# NMX-201-B.net
KiCad netlist of a schematic drawn in EAGLE
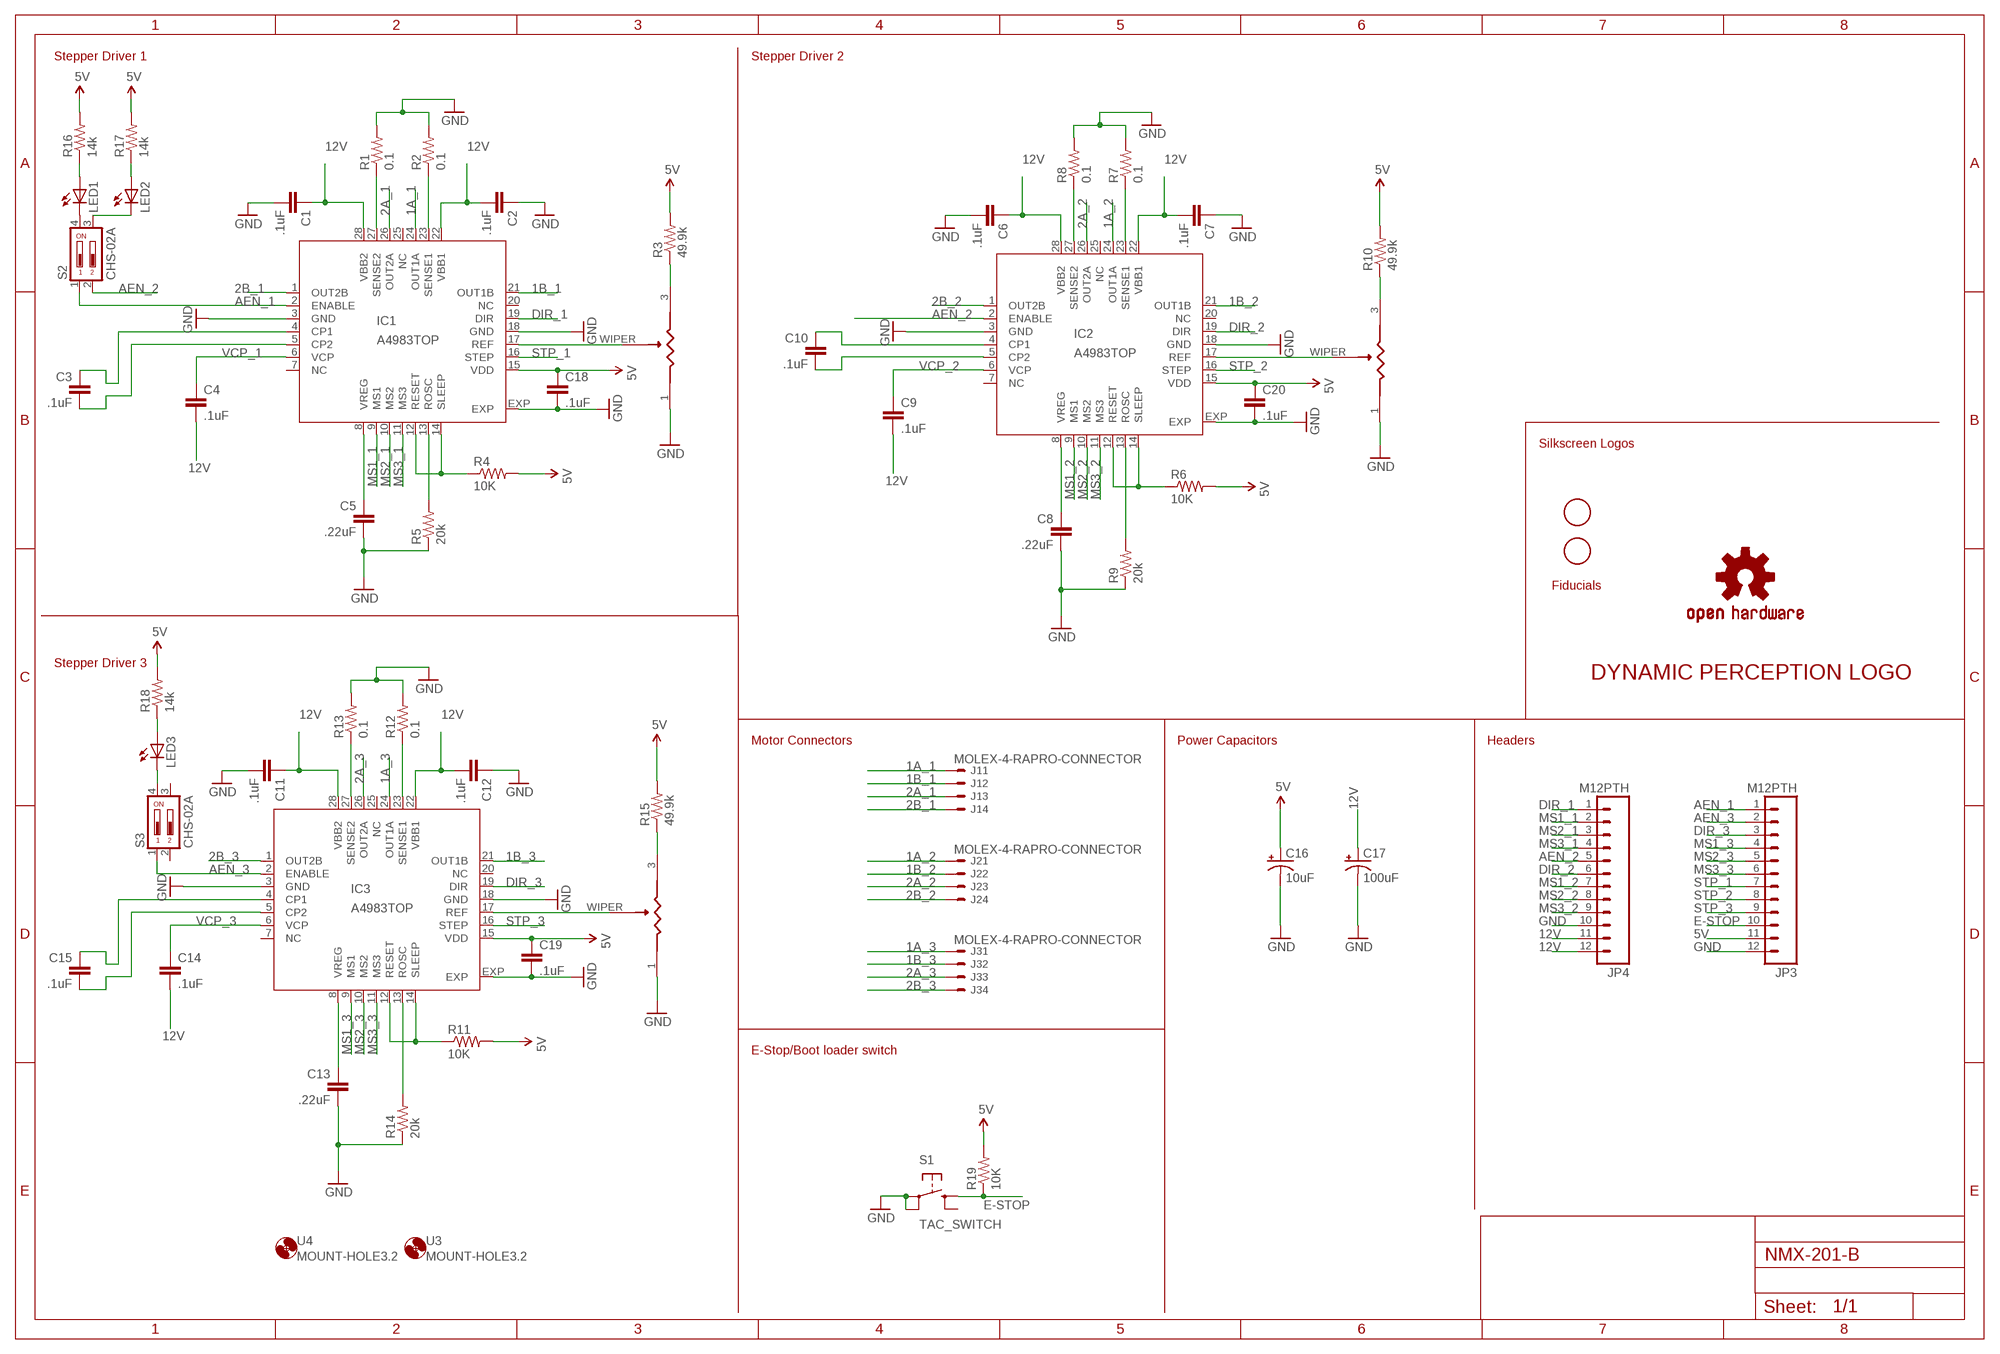
[diagram p0: schematic, sheet 1]

(export (version "E")
  (design (tool "Eeschema 10.0.6"))
  (components
    (comp (ref "C1")
      (value ".1uF")
      (footprint "eagle-import:0402-CAP")
      (fields (field (name "MF") "Taiyo Yuden") (field (name "MPN") "TMK105BJ104KV-F"))
      (libsource (lib "eagle-import") (part "CAP0402-CAP"))
    )
    (comp (ref "C2")
      (value ".1uF")
      (footprint "eagle-import:0402-CAP")
      (fields (field (name "MF") "Taiyo Yuden") (field (name "MPN") "TMK105BJ104KV-F"))
      (libsource (lib "eagle-import") (part "CAP0402-CAP"))
    )
    (comp (ref "C3")
      (value ".1uF")
      (footprint "eagle-import:0402-CAP")
      (fields (field (name "MF") "Taiyo Yuden") (field (name "MPN") "TMK105BJ104KV-F"))
      (libsource (lib "eagle-import") (part "CAP0402-CAP"))
    )
    (comp (ref "C4")
      (value ".1uF")
      (footprint "eagle-import:0402-CAP")
      (fields (field (name "MF") "Taiyo Yuden") (field (name "MPN") "TMK105BJ104KV-F"))
      (libsource (lib "eagle-import") (part "CAP0402-CAP"))
    )
    (comp (ref "C5")
      (value ".22uF")
      (footprint "eagle-import:0402-CAP")
      (fields (field (name "MF") "Taiyo Yuden") (field (name "MPN") "TMK105BJ224KVHF"))
      (libsource (lib "eagle-import") (part "CAP0402-CAP"))
    )
    (comp (ref "C6")
      (value ".1uF")
      (footprint "eagle-import:0402-CAP")
      (fields (field (name "MF") "Taiyo Yuden") (field (name "MPN") "TMK105BJ104KV-F"))
      (libsource (lib "eagle-import") (part "CAP0402-CAP"))
    )
    (comp (ref "C7")
      (value ".1uF")
      (footprint "eagle-import:0402-CAP")
      (fields (field (name "MF") "Taiyo Yuden") (field (name "MPN") "TMK105BJ104KV-F"))
      (libsource (lib "eagle-import") (part "CAP0402-CAP"))
    )
    (comp (ref "C8")
      (value ".22uF")
      (footprint "eagle-import:0402-CAP")
      (fields (field (name "MF") "Taiyo Yuden") (field (name "MPN") "TMK105BJ224KVHF"))
      (libsource (lib "eagle-import") (part "CAP0402-CAP"))
    )
    (comp (ref "C9")
      (value ".1uF")
      (footprint "eagle-import:0402-CAP")
      (fields (field (name "MF") "Taiyo Yuden") (field (name "MPN") "TMK105BJ104KV-F"))
      (libsource (lib "eagle-import") (part "CAP0402-CAP"))
    )
    (comp (ref "C10")
      (value ".1uF")
      (footprint "eagle-import:0402-CAP")
      (fields (field (name "MF") "Taiyo Yuden") (field (name "MPN") "TMK105BJ104KV-F"))
      (libsource (lib "eagle-import") (part "CAP0402-CAP"))
    )
    (comp (ref "C11")
      (value ".1uF")
      (footprint "eagle-import:0402-CAP")
      (fields (field (name "MF") "Taiyo Yuden") (field (name "MPN") "TMK105BJ104KV-F"))
      (libsource (lib "eagle-import") (part "CAP0402-CAP"))
    )
    (comp (ref "C12")
      (value ".1uF")
      (footprint "eagle-import:0402-CAP")
      (fields (field (name "MF") "Taiyo Yuden") (field (name "MPN") "TMK105BJ104KV-F"))
      (libsource (lib "eagle-import") (part "CAP0402-CAP"))
    )
    (comp (ref "C13")
      (value ".22uF")
      (footprint "eagle-import:0402-CAP")
      (fields (field (name "MF") "Taiyo Yuden") (field (name "MPN") "TMK105BJ224KVHF"))
      (libsource (lib "eagle-import") (part "CAP0402-CAP"))
    )
    (comp (ref "C14")
      (value ".1uF")
      (footprint "eagle-import:0402-CAP")
      (fields (field (name "MF") "Taiyo Yuden") (field (name "MPN") "TMK105BJ104KV-F"))
      (libsource (lib "eagle-import") (part "CAP0402-CAP"))
    )
    (comp (ref "C15")
      (value ".1uF")
      (footprint "eagle-import:0402-CAP")
      (fields (field (name "MF") "Taiyo Yuden") (field (name "MPN") "TMK105BJ104KV-F"))
      (libsource (lib "eagle-import") (part "CAP0402-CAP"))
    )
    (comp (ref "C16")
      (value "10uF")
      (footprint "eagle-import:EIA3216")
      (fields (field (name "MF") "Kemet") (field (name "MPN") "T491A106M016AT"))
      (libsource (lib "eagle-import") (part "CAP_POL1206"))
    )
    (comp (ref "C17")
      (value "100uF")
      (footprint "eagle-import:PANASONIC_D")
      (fields (field (name "MF") "Panasonic Electronic Components") (field (name "MPN") "EEE-1EA101XP"))
      (libsource (lib "eagle-import") (part "CAP_POLD"))
    )
    (comp (ref "C18")
      (value ".1uF")
      (footprint "eagle-import:0402-CAP")
      (fields (field (name "MF") "Taiyo Yuden") (field (name "MPN") "TMK105BJ104KV-F"))
      (libsource (lib "eagle-import") (part "CAP0402-CAP"))
    )
    (comp (ref "C19")
      (value ".1uF")
      (footprint "eagle-import:0402-CAP")
      (fields (field (name "MF") "Taiyo Yuden") (field (name "MPN") "TMK105BJ104KV-F"))
      (libsource (lib "eagle-import") (part "CAP0402-CAP"))
    )
    (comp (ref "C20")
      (value ".1uF")
      (footprint "eagle-import:0402-CAP")
      (fields (field (name "MF") "Taiyo Yuden") (field (name "MPN") "TMK105BJ104KV-F"))
      (libsource (lib "eagle-import") (part "CAP0402-CAP"))
    )
    (comp (ref "FRAME2")
      (value "A3L-LOCSILK_SCREEN")
      (footprint "eagle-import:DRAWING_NAME")
      (libsource (lib "eagle-import") (part "A3L-LOCSILK_SCREEN"))
    )
    (comp (ref "IC1")
      (value "A4983TOP")
      (footprint "eagle-import:QFN28ET")
      (fields (field (name "MPN") "A4983SETTR-T") (field (name "MPN_1") "A4983SETTR-T"))
      (libsource (lib "eagle-import") (part "A4983TOP"))
    )
    (comp (ref "IC2")
      (value "A4983TOP")
      (footprint "eagle-import:QFN28ET")
      (fields (field (name "MPN") "A4983SETTR-T") (field (name "MPN_1") "A4983SETTR-T"))
      (libsource (lib "eagle-import") (part "A4983TOP"))
    )
    (comp (ref "IC3")
      (value "A4983TOP")
      (footprint "eagle-import:QFN28ET")
      (fields (field (name "MPN") "A4983SETTR-T") (field (name "MPN_1") "A4983SETTR-T"))
      (libsource (lib "eagle-import") (part "A4983TOP"))
    )
    (comp (ref "J1")
      (value "MOLEX-4-RAPRO-CONNECTOR")
      (footprint "eagle-import:PRO_CONNECTOR")
      (fields (field (name "MF") "Molex Inc") (field (name "MPN") "0022053041"))
      (libsource (lib "eagle-import") (part "MOLEX-4-RAPRO-CONNECTOR"))
    )
    (comp (ref "J2")
      (value "MOLEX-4-RAPRO-CONNECTOR")
      (footprint "eagle-import:PRO_CONNECTOR")
      (fields (field (name "MF") "Molex Inc") (field (name "MPN") "0022053041"))
      (libsource (lib "eagle-import") (part "MOLEX-4-RAPRO-CONNECTOR"))
    )
    (comp (ref "J3")
      (value "MOLEX-4-RAPRO-CONNECTOR")
      (footprint "eagle-import:PRO_CONNECTOR")
      (fields (field (name "MF") "Molex Inc") (field (name "MPN") "0022053041"))
      (libsource (lib "eagle-import") (part "MOLEX-4-RAPRO-CONNECTOR"))
    )
    (comp (ref "JP3")
      (value "M12PTH")
      (footprint "eagle-import:1X12")
      (fields (field (name "MF") "Molex Inc") (field (name "MPN") "0901200132"))
      (libsource (lib "eagle-import") (part "M12PTH"))
    )
    (comp (ref "JP4")
      (value "M12PTH")
      (footprint "eagle-import:1X12")
      (fields (field (name "MF") "Molex Inc") (field (name "MPN") "0901200132"))
      (libsource (lib "eagle-import") (part "M12PTH"))
    )
    (comp (ref "LED1")
      (value "LED0603")
      (footprint "eagle-import:LED-0603")
      (fields (field (name "MF") "OSRAM Opto Semiconductors Inc") (field (name "MPN") "LB Q39G-L2N2-35-1"))
      (libsource (lib "eagle-import") (part "LED0603"))
    )
    (comp (ref "LED2")
      (value "LED0603")
      (footprint "eagle-import:LED-0603")
      (fields (field (name "MF") "OSRAM Opto Semiconductors Inc") (field (name "MPN") "LB Q39G-L2N2-35-1"))
      (libsource (lib "eagle-import") (part "LED0603"))
    )
    (comp (ref "LED3")
      (value "LED0603")
      (footprint "eagle-import:LED-0603")
      (fields (field (name "MF") "OSRAM Opto Semiconductors Inc") (field (name "MPN") "LB Q39G-L2N2-35-1"))
      (libsource (lib "eagle-import") (part "LED0603"))
    )
    (comp (ref "R1")
      (value "0.1")
      (footprint "eagle-import:R0603")
      (fields (field (name "MF") "Samsung Electro-Mechanics America") (field (name "MPN") "RU1608FR100CS"))
      (libsource (lib "eagle-import") (part "R-US_R0603"))
    )
    (comp (ref "R2")
      (value "0.1")
      (footprint "eagle-import:R0603")
      (fields (field (name "MF") "Samsung Electro-Mechanics America") (field (name "MPN") "RU1608FR100CS"))
      (libsource (lib "eagle-import") (part "R-US_R0603"))
    )
    (comp (ref "R3")
      (value "49.9k")
      (footprint "eagle-import:R0402_BOTTOM")
      (fields (field (name "MF") "Yageo") (field (name "MPN") "RC0402FR-0749K9L"))
      (libsource (lib "eagle-import") (part "R-US_R0402_B"))
    )
    (comp (ref "R4")
      (value "10K")
      (footprint "eagle-import:R0402_BOTTOM")
      (fields (field (name "MF") "Yageo") (field (name "MPN") "RC0402FR-0710KL"))
      (libsource (lib "eagle-import") (part "R-US_R0402_B"))
    )
    (comp (ref "R5")
      (value "20k")
      (footprint "eagle-import:R0402_BOTTOM")
      (fields (field (name "MF") "Yageo") (field (name "MPN") "RC0402FR-0720KL"))
      (libsource (lib "eagle-import") (part "R-US_R0402_B"))
    )
    (comp (ref "R6")
      (value "10K")
      (footprint "eagle-import:R0402_BOTTOM")
      (fields (field (name "MF") "Yageo") (field (name "MPN") "RC0402FR-0710KL"))
      (libsource (lib "eagle-import") (part "R-US_R0402_B"))
    )
    (comp (ref "R7")
      (value "0.1")
      (footprint "eagle-import:R0603")
      (fields (field (name "MF") "Samsung Electro-Mechanics America") (field (name "MPN") "RU1608FR100CS"))
      (libsource (lib "eagle-import") (part "R-US_R0603"))
    )
    (comp (ref "R8")
      (value "0.1")
      (footprint "eagle-import:R0603")
      (fields (field (name "MF") "Samsung Electro-Mechanics America") (field (name "MPN") "RU1608FR100CS"))
      (libsource (lib "eagle-import") (part "R-US_R0603"))
    )
    (comp (ref "R9")
      (value "20k")
      (footprint "eagle-import:R0402_BOTTOM")
      (fields (field (name "MF") "Yageo") (field (name "MPN") "RC0402FR-0720KL"))
      (libsource (lib "eagle-import") (part "R-US_R0402_B"))
    )
    (comp (ref "R10")
      (value "49.9k")
      (footprint "eagle-import:R0402_BOTTOM")
      (fields (field (name "MF") "Yageo") (field (name "MPN") "RC0402FR-0749K9L"))
      (libsource (lib "eagle-import") (part "R-US_R0402_B"))
    )
    (comp (ref "R11")
      (value "10K")
      (footprint "eagle-import:R0402_BOTTOM")
      (fields (field (name "MF") "Yageo") (field (name "MPN") "RC0402FR-0710KL"))
      (libsource (lib "eagle-import") (part "R-US_R0402_B"))
    )
    (comp (ref "R12")
      (value "0.1")
      (footprint "eagle-import:R0603")
      (fields (field (name "MF") "Samsung Electro-Mechanics America") (field (name "MPN") "RU1608FR100CS"))
      (libsource (lib "eagle-import") (part "R-US_R0603"))
    )
    (comp (ref "R13")
      (value "0.1")
      (footprint "eagle-import:R0603")
      (fields (field (name "MF") "Samsung Electro-Mechanics America") (field (name "MPN") "RU1608FR100CS"))
      (libsource (lib "eagle-import") (part "R-US_R0603"))
    )
    (comp (ref "R14")
      (value "20k")
      (footprint "eagle-import:R0402_BOTTOM")
      (fields (field (name "MF") "Yageo") (field (name "MPN") "RC0402FR-0720KL"))
      (libsource (lib "eagle-import") (part "R-US_R0402_B"))
    )
    (comp (ref "R15")
      (value "49.9k")
      (footprint "eagle-import:R0402_BOTTOM")
      (fields (field (name "MF") "Yageo") (field (name "MPN") "RC0402FR-0749K9L"))
      (libsource (lib "eagle-import") (part "R-US_R0402_B"))
    )
    (comp (ref "R16")
      (value "14k")
      (footprint "eagle-import:R0402_BOTTOM")
      (fields (field (name "MF") "Yageo") (field (name "MPN") "RC0402FR-0714KL"))
      (libsource (lib "eagle-import") (part "R-US_R0402_B"))
    )
    (comp (ref "R17")
      (value "14k")
      (footprint "eagle-import:R0402_BOTTOM")
      (fields (field (name "MF") "Yageo") (field (name "MPN") "RC0402FR-0714KL"))
      (libsource (lib "eagle-import") (part "R-US_R0402_B"))
    )
    (comp (ref "R18")
      (value "14k")
      (footprint "eagle-import:R0402_BOTTOM")
      (fields (field (name "MF") "Yageo") (field (name "MPN") "RC0402FR-0714KL"))
      (libsource (lib "eagle-import") (part "R-US_R0402_B"))
    )
    (comp (ref "R19")
      (value "10K")
      (footprint "eagle-import:R0402_BOTTOM")
      (fields (field (name "MF") "Yageo") (field (name "MPN") "RC0402FR-0710KL"))
      (libsource (lib "eagle-import") (part "R-US_R0402_B"))
    )
    (comp (ref "S1")
      (value "TAC_SWITCH")
      (footprint "eagle-import:TAC_SWITCH_THR")
      (fields (field (name "MF") "TE Connectivity") (field (name "MPN") "2-1825027-0"))
      (libsource (lib "eagle-import") (part "TAC_SWITCH"))
    )
    (comp (ref "S2")
      (value "CHS-02A")
      (footprint "eagle-import:CHS-02A")
      (libsource (lib "eagle-import") (part "CHS-02A"))
    )
    (comp (ref "S3")
      (value "CHS-02A")
      (footprint "eagle-import:CHS-02A")
      (libsource (lib "eagle-import") (part "CHS-02A"))
    )
    (comp (ref "U$1")
      (value "DP_LOGOMICRO")
      (footprint "eagle-import:DP_LOGO_MICRO")
      (libsource (lib "eagle-import") (part "DP_LOGOMICRO"))
    )
    (comp (ref "U$2")
      (value "OSHW-LOGOS")
      (footprint "eagle-import:OSHW-LOGO-S")
      (libsource (lib "eagle-import") (part "OSHW-LOGOS"))
    )
    (comp (ref "U$3")
      (value "FIDUCIAL")
      (footprint "eagle-import:FIDUCIAL_1MM")
      (libsource (lib "eagle-import") (part "FIDUCIAL"))
    )
    (comp (ref "U$4")
      (value "FIDUCIAL")
      (footprint "eagle-import:FIDUCIAL_1MM")
      (libsource (lib "eagle-import") (part "FIDUCIAL"))
    )
    (comp (ref "U1")
      (value "CADJ")
      (footprint "eagle-import:3MM_SMD")
      (fields (field (name "MF") "Bourns Inc") (field (name "MPN") "TC33X-2-103E"))
      (libsource (lib "eagle-import") (part "TC33X-2"))
    )
    (comp (ref "U2")
      (value "CADJ")
      (footprint "eagle-import:3MM_SMD")
      (fields (field (name "MF") "Bourns Inc") (field (name "MPN") "TC33X-2-103E"))
      (libsource (lib "eagle-import") (part "TC33X-2"))
    )
    (comp (ref "U3")
      (value "MOUNT-HOLE3.2")
      (footprint "eagle-import:3,2")
      (libsource (lib "eagle-import") (part "MOUNT-HOLE3.2"))
    )
    (comp (ref "U4")
      (value "MOUNT-HOLE3.2")
      (footprint "eagle-import:3,2")
      (libsource (lib "eagle-import") (part "MOUNT-HOLE3.2"))
    )
    (comp (ref "U5")
      (value "CADJ")
      (footprint "eagle-import:3MM_SMD")
      (fields (field (name "MF") "Bourns Inc") (field (name "MPN") "TC33X-2-103E"))
      (libsource (lib "eagle-import") (part "TC33X-2"))
    )
  )
  (nets
    (net (code "1") (name "/1A_1") (class "Default")
      (node (ref "IC1") (pin "24") (pinfunction "OUT1A_24") (pintype "output"))
      (node (ref "J1") (pin "P$1") (pinfunction "S_P$1") (pintype "passive"))
    )
    (net (code "2") (name "/1A_2") (class "Default")
      (node (ref "IC2") (pin "24") (pinfunction "OUT1A_24") (pintype "output"))
      (node (ref "J2") (pin "P$1") (pinfunction "S_P$1") (pintype "passive"))
    )
    (net (code "3") (name "/1A_3") (class "Default")
      (node (ref "IC3") (pin "24") (pinfunction "OUT1A_24") (pintype "output"))
      (node (ref "J3") (pin "P$1") (pinfunction "S_P$1") (pintype "passive"))
    )
    (net (code "4") (name "/1B_1") (class "Default")
      (node (ref "IC1") (pin "21") (pinfunction "OUT1B_21") (pintype "output"))
      (node (ref "J1") (pin "P$2") (pinfunction "S_P$2") (pintype "passive"))
    )
    (net (code "5") (name "/1B_2") (class "Default")
      (node (ref "IC2") (pin "21") (pinfunction "OUT1B_21") (pintype "output"))
      (node (ref "J2") (pin "P$2") (pinfunction "S_P$2") (pintype "passive"))
    )
    (net (code "6") (name "/1B_3") (class "Default")
      (node (ref "IC3") (pin "21") (pinfunction "OUT1B_21") (pintype "output"))
      (node (ref "J3") (pin "P$2") (pinfunction "S_P$2") (pintype "passive"))
    )
    (net (code "7") (name "/2A_1") (class "Default")
      (node (ref "IC1") (pin "26") (pinfunction "OUT2A_26") (pintype "output"))
      (node (ref "J1") (pin "P$3") (pinfunction "S_P$3") (pintype "passive"))
    )
    (net (code "8") (name "/2A_2") (class "Default")
      (node (ref "IC2") (pin "26") (pinfunction "OUT2A_26") (pintype "output"))
      (node (ref "J2") (pin "P$3") (pinfunction "S_P$3") (pintype "passive"))
    )
    (net (code "9") (name "/2A_3") (class "Default")
      (node (ref "IC3") (pin "26") (pinfunction "OUT2A_26") (pintype "output"))
      (node (ref "J3") (pin "P$3") (pinfunction "S_P$3") (pintype "passive"))
    )
    (net (code "10") (name "/2B_1") (class "Default")
      (node (ref "IC1") (pin "1") (pinfunction "OUT2B_1") (pintype "output"))
      (node (ref "J1") (pin "P$4") (pinfunction "S_P$4") (pintype "passive"))
    )
    (net (code "11") (name "/2B_2") (class "Default")
      (node (ref "IC2") (pin "1") (pinfunction "OUT2B_1") (pintype "output"))
      (node (ref "J2") (pin "P$4") (pinfunction "S_P$4") (pintype "passive"))
    )
    (net (code "12") (name "/2B_3") (class "Default")
      (node (ref "IC3") (pin "1") (pinfunction "OUT2B_1") (pintype "output"))
      (node (ref "J3") (pin "P$4") (pinfunction "S_P$4") (pintype "passive"))
    )
    (net (code "13") (name "/12V") (class "Default")
      (node (ref "C1") (pin "1") (pinfunction "1_1") (pintype "passive"))
      (node (ref "C11") (pin "1") (pinfunction "1_1") (pintype "passive"))
      (node (ref "C12") (pin "2") (pinfunction "2_2") (pintype "passive"))
      (node (ref "C14") (pin "2") (pinfunction "2_2") (pintype "passive"))
      (node (ref "C17") (pin "+") (pinfunction "+_+") (pintype "passive"))
      (node (ref "C2") (pin "2") (pinfunction "2_2") (pintype "passive"))
      (node (ref "C4") (pin "2") (pinfunction "2_2") (pintype "passive"))
      (node (ref "C6") (pin "1") (pinfunction "1_1") (pintype "passive"))
      (node (ref "C7") (pin "2") (pinfunction "2_2") (pintype "passive"))
      (node (ref "C9") (pin "2") (pinfunction "2_2") (pintype "passive"))
      (node (ref "IC1") (pin "22") (pinfunction "VBB1_22") (pintype "power_in"))
      (node (ref "IC1") (pin "28") (pinfunction "VBB2_28") (pintype "power_in"))
      (node (ref "IC2") (pin "22") (pinfunction "VBB1_22") (pintype "power_in"))
      (node (ref "IC2") (pin "28") (pinfunction "VBB2_28") (pintype "power_in"))
      (node (ref "IC3") (pin "22") (pinfunction "VBB1_22") (pintype "power_in"))
      (node (ref "IC3") (pin "28") (pinfunction "VBB2_28") (pintype "power_in"))
      (node (ref "JP4") (pin "11") (pinfunction "11_11") (pintype "passive"))
      (node (ref "JP4") (pin "12") (pinfunction "12_12") (pintype "passive"))
    )
    (net (code "14") (name "/AEN_1") (class "Default")
      (node (ref "IC1") (pin "2") (pinfunction "ENABLE_2") (pintype "input"))
      (node (ref "JP3") (pin "1") (pinfunction "1_1") (pintype "passive"))
      (node (ref "S2") (pin "1") (pinfunction "1_1") (pintype "passive"))
    )
    (net (code "15") (name "/AEN_2") (class "Default")
      (node (ref "IC2") (pin "2") (pinfunction "ENABLE_2") (pintype "input"))
      (node (ref "JP4") (pin "5") (pinfunction "5_5") (pintype "passive"))
      (node (ref "S2") (pin "2") (pinfunction "2_2") (pintype "passive"))
    )
    (net (code "16") (name "/AEN_3") (class "Default")
      (node (ref "IC3") (pin "2") (pinfunction "ENABLE_2") (pintype "input"))
      (node (ref "JP3") (pin "2") (pinfunction "2_2") (pintype "passive"))
      (node (ref "S3") (pin "1") (pinfunction "1_1") (pintype "passive"))
    )
    (net (code "17") (name "/DIR_1") (class "Default")
      (node (ref "IC1") (pin "19") (pinfunction "DIR_19") (pintype "input"))
      (node (ref "JP4") (pin "1") (pinfunction "1_1") (pintype "passive"))
    )
    (net (code "18") (name "/DIR_2") (class "Default")
      (node (ref "IC2") (pin "19") (pinfunction "DIR_19") (pintype "input"))
      (node (ref "JP4") (pin "6") (pinfunction "6_6") (pintype "passive"))
    )
    (net (code "19") (name "/DIR_3") (class "Default")
      (node (ref "IC3") (pin "19") (pinfunction "DIR_19") (pintype "input"))
      (node (ref "JP3") (pin "3") (pinfunction "3_3") (pintype "passive"))
    )
    (net (code "20") (name "/E-STOP") (class "Default")
      (node (ref "JP3") (pin "10") (pinfunction "10_10") (pintype "passive"))
      (node (ref "R19") (pin "1") (pinfunction "1_1") (pintype "passive"))
      (node (ref "S1") (pin "B") (pinfunction "3_B") (pintype "passive"))
    )
    (net (code "21") (name "/MS1_1") (class "Default")
      (node (ref "IC1") (pin "9") (pinfunction "MS1_9") (pintype "input"))
      (node (ref "JP4") (pin "2") (pinfunction "2_2") (pintype "passive"))
    )
    (net (code "22") (name "/MS1_2") (class "Default")
      (node (ref "IC2") (pin "9") (pinfunction "MS1_9") (pintype "input"))
      (node (ref "JP4") (pin "7") (pinfunction "7_7") (pintype "passive"))
    )
    (net (code "23") (name "/MS1_3") (class "Default")
      (node (ref "IC3") (pin "9") (pinfunction "MS1_9") (pintype "input"))
      (node (ref "JP3") (pin "4") (pinfunction "4_4") (pintype "passive"))
    )
    (net (code "24") (name "/MS2_1") (class "Default")
      (node (ref "IC1") (pin "10") (pinfunction "MS2_10") (pintype "input"))
      (node (ref "JP4") (pin "3") (pinfunction "3_3") (pintype "passive"))
    )
    (net (code "25") (name "/MS2_2") (class "Default")
      (node (ref "IC2") (pin "10") (pinfunction "MS2_10") (pintype "input"))
      (node (ref "JP4") (pin "8") (pinfunction "8_8") (pintype "passive"))
    )
    (net (code "26") (name "/MS2_3") (class "Default")
      (node (ref "IC3") (pin "10") (pinfunction "MS2_10") (pintype "input"))
      (node (ref "JP3") (pin "5") (pinfunction "5_5") (pintype "passive"))
    )
    (net (code "27") (name "/MS3_1") (class "Default")
      (node (ref "IC1") (pin "11") (pinfunction "MS3_11") (pintype "input"))
      (node (ref "JP4") (pin "4") (pinfunction "4_4") (pintype "passive"))
    )
    (net (code "28") (name "/MS3_2") (class "Default")
      (node (ref "IC2") (pin "11") (pinfunction "MS3_11") (pintype "input"))
      (node (ref "JP4") (pin "9") (pinfunction "9_9") (pintype "passive"))
    )
    (net (code "29") (name "/MS3_3") (class "Default")
      (node (ref "IC3") (pin "11") (pinfunction "MS3_11") (pintype "input"))
      (node (ref "JP3") (pin "6") (pinfunction "6_6") (pintype "passive"))
    )
    (net (code "30") (name "/STP_1") (class "Default")
      (node (ref "IC1") (pin "16") (pinfunction "STEP_16") (pintype "input"))
      (node (ref "JP3") (pin "7") (pinfunction "7_7") (pintype "passive"))
    )
    (net (code "31") (name "/STP_2") (class "Default")
      (node (ref "IC2") (pin "16") (pinfunction "STEP_16") (pintype "input"))
      (node (ref "JP3") (pin "8") (pinfunction "8_8") (pintype "passive"))
    )
    (net (code "32") (name "/STP_3") (class "Default")
      (node (ref "IC3") (pin "16") (pinfunction "STEP_16") (pintype "input"))
      (node (ref "JP3") (pin "9") (pinfunction "9_9") (pintype "passive"))
    )
    (net (code "33") (name "/VCP_1") (class "Default")
      (node (ref "C4") (pin "1") (pinfunction "1_1") (pintype "passive"))
      (node (ref "IC1") (pin "6") (pinfunction "VCP_6") (pintype "passive"))
    )
    (net (code "34") (name "/VCP_2") (class "Default")
      (node (ref "C9") (pin "1") (pinfunction "1_1") (pintype "passive"))
      (node (ref "IC2") (pin "6") (pinfunction "VCP_6") (pintype "passive"))
    )
    (net (code "35") (name "/VCP_3") (class "Default")
      (node (ref "C14") (pin "1") (pinfunction "1_1") (pintype "passive"))
      (node (ref "IC3") (pin "6") (pinfunction "VCP_6") (pintype "passive"))
    )
    (net (code "36") (name "5V") (class "Default")
      (node (ref "C16") (pin "A") (pinfunction "+_A") (pintype "passive"))
      (node (ref "C18") (pin "1") (pinfunction "1_1") (pintype "passive"))
      (node (ref "C19") (pin "1") (pinfunction "1_1") (pintype "passive"))
      (node (ref "C20") (pin "1") (pinfunction "1_1") (pintype "passive"))
      (node (ref "IC1") (pin "15") (pinfunction "VDD_15") (pintype "power_in"))
      (node (ref "IC2") (pin "15") (pinfunction "VDD_15") (pintype "power_in"))
      (node (ref "IC3") (pin "15") (pinfunction "VDD_15") (pintype "power_in"))
      (node (ref "JP3") (pin "11") (pinfunction "11_11") (pintype "passive"))
      (node (ref "R10") (pin "2") (pinfunction "2_2") (pintype "passive"))
      (node (ref "R11") (pin "2") (pinfunction "2_2") (pintype "passive"))
      (node (ref "R15") (pin "2") (pinfunction "2_2") (pintype "passive"))
      (node (ref "R16") (pin "2") (pinfunction "2_2") (pintype "passive"))
      (node (ref "R17") (pin "2") (pinfunction "2_2") (pintype "passive"))
      (node (ref "R18") (pin "2") (pinfunction "2_2") (pintype "passive"))
      (node (ref "R19") (pin "2") (pinfunction "2_2") (pintype "passive"))
      (node (ref "R3") (pin "2") (pinfunction "2_2") (pintype "passive"))
      (node (ref "R4") (pin "2") (pinfunction "2_2") (pintype "passive"))
      (node (ref "R6") (pin "2") (pinfunction "2_2") (pintype "passive"))
    )
    (net (code "37") (name "GND") (class "Default")
      (node (ref "C1") (pin "2") (pinfunction "2_2") (pintype "passive"))
      (node (ref "C11") (pin "2") (pinfunction "2_2") (pintype "passive"))
      (node (ref "C12") (pin "1") (pinfunction "1_1") (pintype "passive"))
      (node (ref "C13") (pin "2") (pinfunction "2_2") (pintype "passive"))
      (node (ref "C16") (pin "C") (pinfunction "-_C") (pintype "passive"))
      (node (ref "C17") (pin "-") (pinfunction "-_-") (pintype "passive"))
      (node (ref "C18") (pin "2") (pinfunction "2_2") (pintype "passive"))
      (node (ref "C19") (pin "2") (pinfunction "2_2") (pintype "passive"))
      (node (ref "C2") (pin "1") (pinfunction "1_1") (pintype "passive"))
      (node (ref "C20") (pin "2") (pinfunction "2_2") (pintype "passive"))
      (node (ref "C5") (pin "2") (pinfunction "2_2") (pintype "passive"))
      (node (ref "C6") (pin "2") (pinfunction "2_2") (pintype "passive"))
      (node (ref "C7") (pin "1") (pinfunction "1_1") (pintype "passive"))
      (node (ref "C8") (pin "2") (pinfunction "2_2") (pintype "passive"))
      (node (ref "IC1") (pin "18") (pinfunction "GND_18") (pintype "power_in"))
      (node (ref "IC1") (pin "3") (pinfunction "GND_3") (pintype "power_in"))
      (node (ref "IC1") (pin "EXP") (pinfunction "EXP_EXP") (pintype "passive"))
      (node (ref "IC2") (pin "18") (pinfunction "GND_18") (pintype "power_in"))
      (node (ref "IC2") (pin "3") (pinfunction "GND_3") (pintype "power_in"))
      (node (ref "IC2") (pin "EXP") (pinfunction "EXP_EXP") (pintype "passive"))
      (node (ref "IC3") (pin "18") (pinfunction "GND_18") (pintype "power_in"))
      (node (ref "IC3") (pin "3") (pinfunction "GND_3") (pintype "power_in"))
      (node (ref "IC3") (pin "EXP") (pinfunction "EXP_EXP") (pintype "passive"))
      (node (ref "JP3") (pin "12") (pinfunction "12_12") (pintype "passive"))
      (node (ref "JP4") (pin "10") (pinfunction "10_10") (pintype "passive"))
      (node (ref "R1") (pin "2") (pinfunction "2_2") (pintype "passive"))
      (node (ref "R12") (pin "2") (pinfunction "2_2") (pintype "passive"))
      (node (ref "R13") (pin "2") (pinfunction "2_2") (pintype "passive"))
      (node (ref "R14") (pin "1") (pinfunction "1_1") (pintype "passive"))
      (node (ref "R2") (pin "2") (pinfunction "2_2") (pintype "passive"))
      (node (ref "R5") (pin "1") (pinfunction "1_1") (pintype "passive"))
      (node (ref "R7") (pin "2") (pinfunction "2_2") (pintype "passive"))
      (node (ref "R8") (pin "2") (pinfunction "2_2") (pintype "passive"))
      (node (ref "R9") (pin "1") (pinfunction "1_1") (pintype "passive"))
      (node (ref "S1") (pin "A") (pinfunction "1_A") (pintype "passive"))
      (node (ref "S1") (pin "P$1") (pinfunction "2_P$1") (pintype "passive"))
      (node (ref "U1") (pin "1") (pinfunction "1_1") (pintype "bidirectional"))
      (node (ref "U2") (pin "1") (pinfunction "1_1") (pintype "bidirectional"))
      (node (ref "U5") (pin "1") (pinfunction "1_1") (pintype "bidirectional"))
    )
    (net (code "38") (name "Net-(IC1-CP1)") (class "Default")
      (node (ref "C3") (pin "1") (pinfunction "1_1") (pintype "passive"))
      (node (ref "IC1") (pin "4") (pinfunction "CP1_4") (pintype "passive"))
    )
    (net (code "39") (name "Net-(IC1-CP2)") (class "Default")
      (node (ref "C3") (pin "2") (pinfunction "2_2") (pintype "passive"))
      (node (ref "IC1") (pin "5") (pinfunction "CP2_5") (pintype "passive"))
    )
    (net (code "40") (name "Net-(IC1-REF)") (class "Default")
      (node (ref "IC1") (pin "17") (pinfunction "REF_17") (pintype "input"))
      (node (ref "U1") (pin "WIPER") (pinfunction "2_WIPER") (pintype "bidirectional"))
    )
    (net (code "41") (name "Net-(IC1-RESET)") (class "Default")
      (node (ref "IC1") (pin "12") (pinfunction "RESET_12") (pintype "input"))
      (node (ref "IC1") (pin "14") (pinfunction "SLEEP_14") (pintype "input"))
      (node (ref "R4") (pin "1") (pinfunction "1_1") (pintype "passive"))
    )
    (net (code "42") (name "Net-(IC1-ROSC)") (class "Default")
      (node (ref "IC1") (pin "13") (pinfunction "ROSC_13") (pintype "input"))
      (node (ref "R5") (pin "2") (pinfunction "2_2") (pintype "passive"))
    )
    (net (code "43") (name "Net-(IC1-SENSE1)") (class "Default")
      (node (ref "IC1") (pin "23") (pinfunction "SENSE1_23") (pintype "input"))
      (node (ref "R2") (pin "1") (pinfunction "1_1") (pintype "passive"))
    )
    (net (code "44") (name "Net-(IC1-SENSE2)") (class "Default")
      (node (ref "IC1") (pin "27") (pinfunction "SENSE2_27") (pintype "input"))
      (node (ref "R1") (pin "1") (pinfunction "1_1") (pintype "passive"))
    )
    (net (code "45") (name "Net-(IC1-VREG)") (class "Default")
      (node (ref "C5") (pin "1") (pinfunction "1_1") (pintype "passive"))
      (node (ref "IC1") (pin "8") (pinfunction "VREG_8") (pintype "passive"))
    )
    (net (code "46") (name "Net-(IC2-CP1)") (class "Default")
      (node (ref "C10") (pin "1") (pinfunction "1_1") (pintype "passive"))
      (node (ref "IC2") (pin "4") (pinfunction "CP1_4") (pintype "passive"))
    )
    (net (code "47") (name "Net-(IC2-CP2)") (class "Default")
      (node (ref "C10") (pin "2") (pinfunction "2_2") (pintype "passive"))
      (node (ref "IC2") (pin "5") (pinfunction "CP2_5") (pintype "passive"))
    )
    (net (code "48") (name "Net-(IC2-REF)") (class "Default")
      (node (ref "IC2") (pin "17") (pinfunction "REF_17") (pintype "input"))
      (node (ref "U2") (pin "WIPER") (pinfunction "2_WIPER") (pintype "bidirectional"))
    )
    (net (code "49") (name "Net-(IC2-RESET)") (class "Default")
      (node (ref "IC2") (pin "12") (pinfunction "RESET_12") (pintype "input"))
      (node (ref "IC2") (pin "14") (pinfunction "SLEEP_14") (pintype "input"))
      (node (ref "R6") (pin "1") (pinfunction "1_1") (pintype "passive"))
    )
    (net (code "50") (name "Net-(IC2-ROSC)") (class "Default")
      (node (ref "IC2") (pin "13") (pinfunction "ROSC_13") (pintype "input"))
      (node (ref "R9") (pin "2") (pinfunction "2_2") (pintype "passive"))
    )
    (net (code "51") (name "Net-(IC2-SENSE1)") (class "Default")
      (node (ref "IC2") (pin "23") (pinfunction "SENSE1_23") (pintype "input"))
      (node (ref "R7") (pin "1") (pinfunction "1_1") (pintype "passive"))
    )
    (net (code "52") (name "Net-(IC2-SENSE2)") (class "Default")
      (node (ref "IC2") (pin "27") (pinfunction "SENSE2_27") (pintype "input"))
      (node (ref "R8") (pin "1") (pinfunction "1_1") (pintype "passive"))
    )
    (net (code "53") (name "Net-(IC2-VREG)") (class "Default")
      (node (ref "C8") (pin "1") (pinfunction "1_1") (pintype "passive"))
      (node (ref "IC2") (pin "8") (pinfunction "VREG_8") (pintype "passive"))
    )
    (net (code "54") (name "Net-(IC3-CP1)") (class "Default")
      (node (ref "C15") (pin "1") (pinfunction "1_1") (pintype "passive"))
      (node (ref "IC3") (pin "4") (pinfunction "CP1_4") (pintype "passive"))
    )
    (net (code "55") (name "Net-(IC3-CP2)") (class "Default")
      (node (ref "C15") (pin "2") (pinfunction "2_2") (pintype "passive"))
      (node (ref "IC3") (pin "5") (pinfunction "CP2_5") (pintype "passive"))
    )
    (net (code "56") (name "Net-(IC3-REF)") (class "Default")
      (node (ref "IC3") (pin "17") (pinfunction "REF_17") (pintype "input"))
      (node (ref "U5") (pin "WIPER") (pinfunction "2_WIPER") (pintype "bidirectional"))
    )
    (net (code "57") (name "Net-(IC3-RESET)") (class "Default")
      (node (ref "IC3") (pin "12") (pinfunction "RESET_12") (pintype "input"))
      (node (ref "IC3") (pin "14") (pinfunction "SLEEP_14") (pintype "input"))
      (node (ref "R11") (pin "1") (pinfunction "1_1") (pintype "passive"))
    )
    (net (code "58") (name "Net-(IC3-ROSC)") (class "Default")
      (node (ref "IC3") (pin "13") (pinfunction "ROSC_13") (pintype "input"))
      (node (ref "R14") (pin "2") (pinfunction "2_2") (pintype "passive"))
    )
    (net (code "59") (name "Net-(IC3-SENSE1)") (class "Default")
      (node (ref "IC3") (pin "23") (pinfunction "SENSE1_23") (pintype "input"))
      (node (ref "R12") (pin "1") (pinfunction "1_1") (pintype "passive"))
    )
    (net (code "60") (name "Net-(IC3-SENSE2)") (class "Default")
      (node (ref "IC3") (pin "27") (pinfunction "SENSE2_27") (pintype "input"))
      (node (ref "R13") (pin "1") (pinfunction "1_1") (pintype "passive"))
    )
    (net (code "61") (name "Net-(IC3-VREG)") (class "Default")
      (node (ref "C13") (pin "1") (pinfunction "1_1") (pintype "passive"))
      (node (ref "IC3") (pin "8") (pinfunction "VREG_8") (pintype "passive"))
    )
    (net (code "62") (name "Net-(LED1-PadA)") (class "Default")
      (node (ref "LED1") (pin "A") (pinfunction "A_A") (pintype "passive"))
      (node (ref "R16") (pin "1") (pinfunction "1_1") (pintype "passive"))
    )
    (net (code "63") (name "Net-(LED1-PadC)") (class "Default")
      (node (ref "LED1") (pin "C") (pinfunction "C_C") (pintype "passive"))
      (node (ref "S2") (pin "4") (pinfunction "4_4") (pintype "passive"))
    )
    (net (code "64") (name "Net-(LED2-PadA)") (class "Default")
      (node (ref "LED2") (pin "A") (pinfunction "A_A") (pintype "passive"))
      (node (ref "R17") (pin "1") (pinfunction "1_1") (pintype "passive"))
    )
    (net (code "65") (name "Net-(LED2-PadC)") (class "Default")
      (node (ref "LED2") (pin "C") (pinfunction "C_C") (pintype "passive"))
      (node (ref "S2") (pin "3") (pinfunction "3_3") (pintype "passive"))
    )
    (net (code "66") (name "Net-(LED3-PadA)") (class "Default")
      (node (ref "LED3") (pin "A") (pinfunction "A_A") (pintype "passive"))
      (node (ref "R18") (pin "1") (pinfunction "1_1") (pintype "passive"))
    )
    (net (code "67") (name "Net-(LED3-PadC)") (class "Default")
      (node (ref "LED3") (pin "C") (pinfunction "C_C") (pintype "passive"))
      (node (ref "S3") (pin "4") (pinfunction "4_4") (pintype "passive"))
    )
    (net (code "68") (name "Net-(R3-Pad1)") (class "Default")
      (node (ref "R3") (pin "1") (pinfunction "1_1") (pintype "passive"))
      (node (ref "U1") (pin "3") (pinfunction "3_3") (pintype "bidirectional"))
    )
    (net (code "69") (name "Net-(R10-Pad1)") (class "Default")
      (node (ref "R10") (pin "1") (pinfunction "1_1") (pintype "passive"))
      (node (ref "U2") (pin "3") (pinfunction "3_3") (pintype "bidirectional"))
    )
    (net (code "70") (name "Net-(R15-Pad1)") (class "Default")
      (node (ref "R15") (pin "1") (pinfunction "1_1") (pintype "passive"))
      (node (ref "U5") (pin "3") (pinfunction "3_3") (pintype "bidirectional"))
    )
    (net (code "71") (name "unconnected-(IC1-NC-Pad7)") (class "Default")
      (node (ref "IC1") (pin "7") (pinfunction "NC_7") (pintype "no_connect"))
    )
    (net (code "72") (name "unconnected-(IC1-NC-Pad20)") (class "Default")
      (node (ref "IC1") (pin "20") (pinfunction "NC_20") (pintype "no_connect"))
    )
    (net (code "73") (name "unconnected-(IC1-NC-Pad25)") (class "Default")
      (node (ref "IC1") (pin "25") (pinfunction "NC_25") (pintype "no_connect"))
    )
    (net (code "74") (name "unconnected-(IC2-NC-Pad7)") (class "Default")
      (node (ref "IC2") (pin "7") (pinfunction "NC_7") (pintype "no_connect"))
    )
    (net (code "75") (name "unconnected-(IC2-NC-Pad20)") (class "Default")
      (node (ref "IC2") (pin "20") (pinfunction "NC_20") (pintype "no_connect"))
    )
    (net (code "76") (name "unconnected-(IC2-NC-Pad25)") (class "Default")
      (node (ref "IC2") (pin "25") (pinfunction "NC_25") (pintype "no_connect"))
    )
    (net (code "77") (name "unconnected-(IC3-NC-Pad7)") (class "Default")
      (node (ref "IC3") (pin "7") (pinfunction "NC_7") (pintype "no_connect"))
    )
    (net (code "78") (name "unconnected-(IC3-NC-Pad20)") (class "Default")
      (node (ref "IC3") (pin "20") (pinfunction "NC_20") (pintype "no_connect"))
    )
    (net (code "79") (name "unconnected-(IC3-NC-Pad25)") (class "Default")
      (node (ref "IC3") (pin "25") (pinfunction "NC_25") (pintype "no_connect"))
    )
    (net (code "80") (name "unconnected-(S1-4-PadP$2)") (class "Default")
      (node (ref "S1") (pin "P$2") (pinfunction "4_P$2") (pintype "passive"))
    )
    (net (code "81") (name "unconnected-(S3-Pad2)") (class "Default")
      (node (ref "S3") (pin "2") (pinfunction "2_2") (pintype "passive"))
    )
    (net (code "82") (name "unconnected-(S3-Pad3)") (class "Default")
      (node (ref "S3") (pin "3") (pinfunction "3_3") (pintype "passive"))
    )
  )
)
